# OSO-MISC-21-008_Hiking_Log.net
KiCad netlist of a schematic drawn in EAGLE
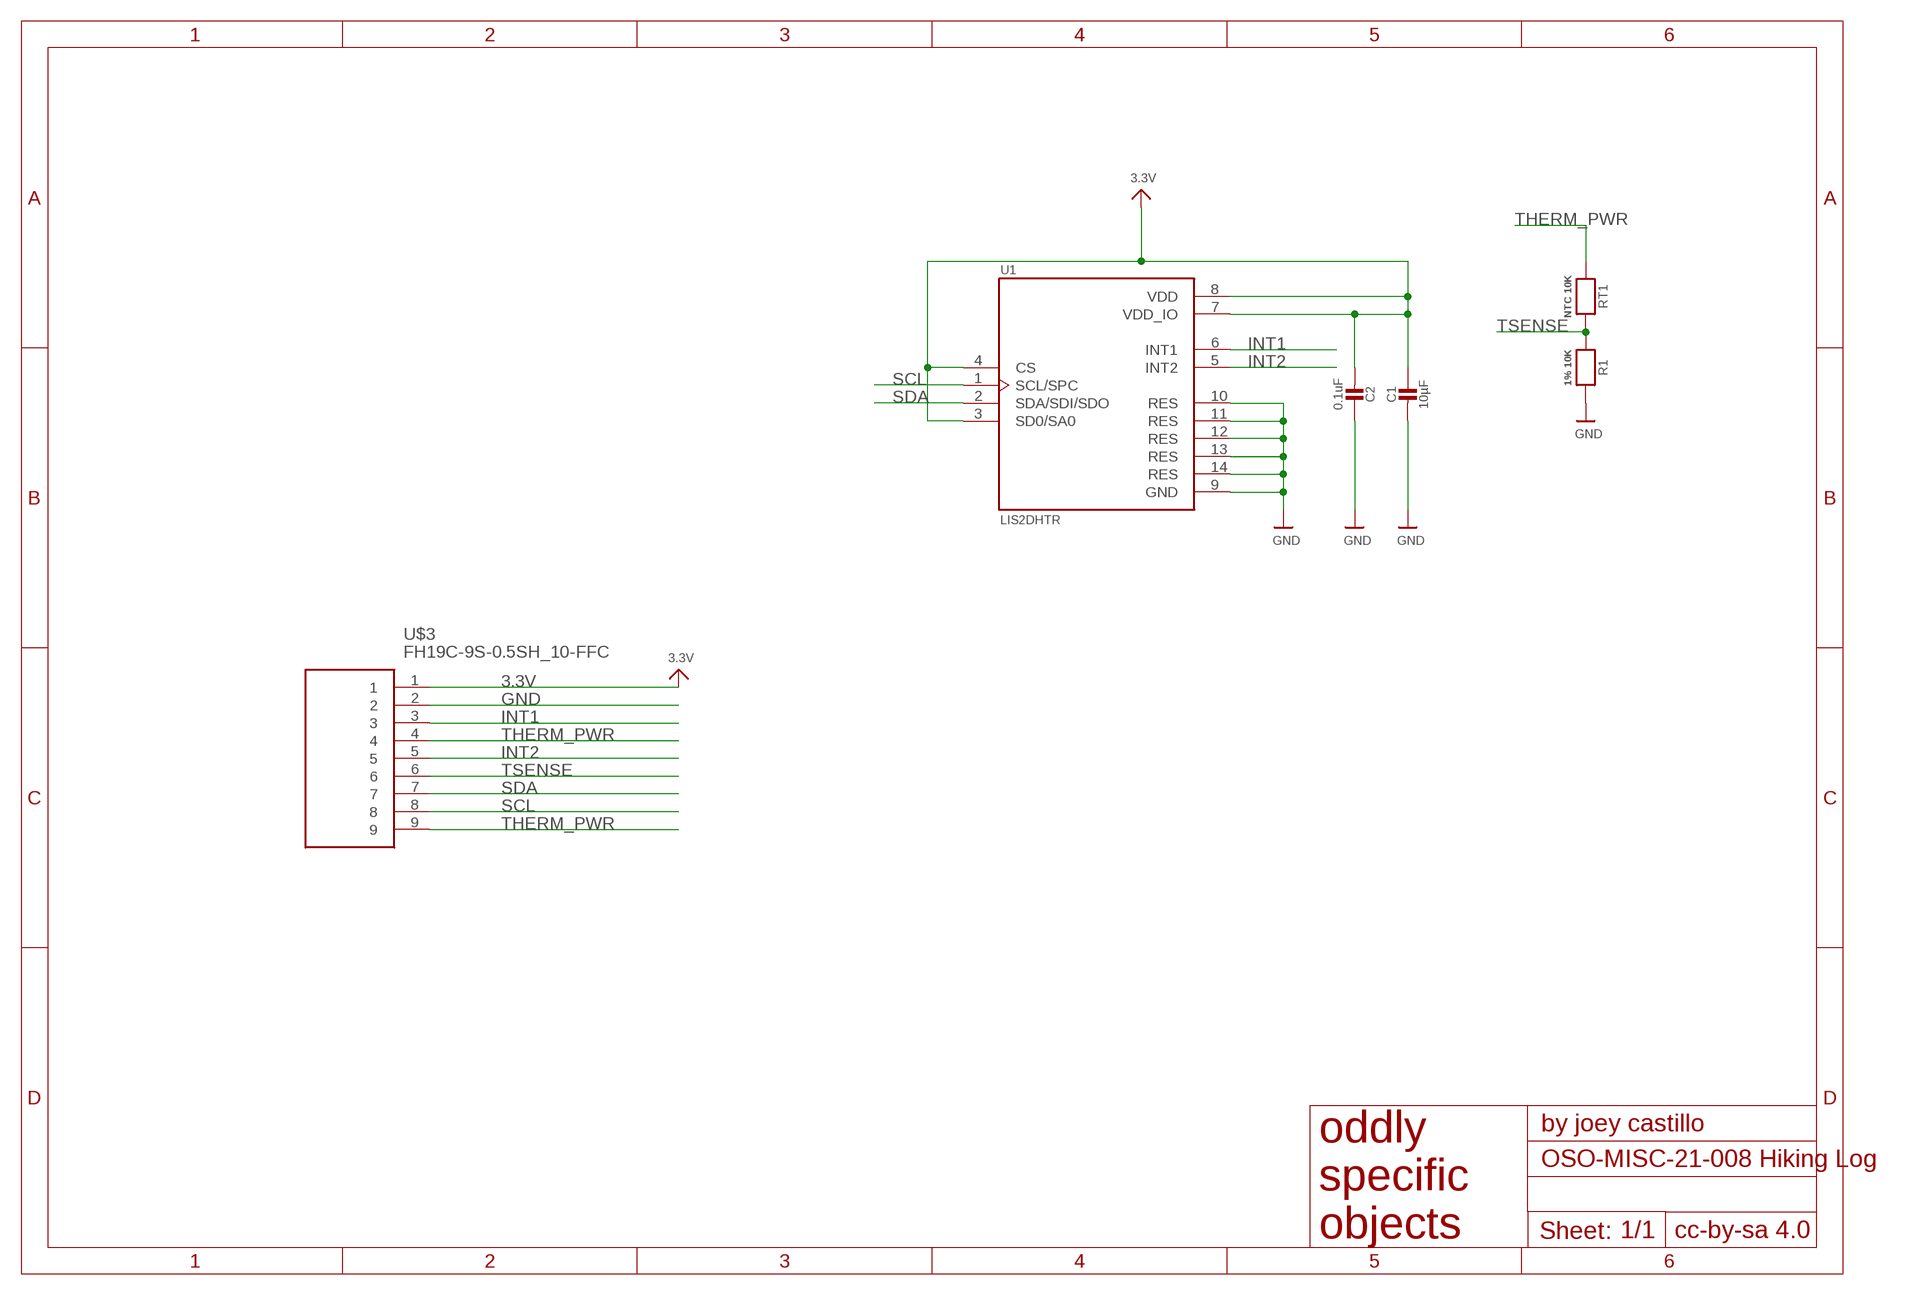
[diagram p0: schematic, sheet 1]

(export (version "E")
  (design (tool "Eeschema 10.0.6"))
  (components
    (comp (ref "C1")
      (value "10µF")
      (footprint "eagle-import:_0402MP")
      (libsource (lib "eagle-import") (part "CAP_CERAMIC_0402MP"))
    )
    (comp (ref "C2")
      (value "0.1uF")
      (footprint "eagle-import:_0402MP")
      (libsource (lib "eagle-import") (part "CAP_CERAMIC_0402MP"))
    )
    (comp (ref "R1")
      (value "1% 10K")
      (footprint "eagle-import:_0402MP")
      (libsource (lib "eagle-import") (part "RESISTOR_0402MP"))
    )
    (comp (ref "RT1")
      (value "NTC 10K")
      (footprint "eagle-import:_0402MP")
      (libsource (lib "eagle-import") (part "RESISTOR_0402MP"))
    )
    (comp (ref "U$3")
      (value "FH19C-9S-0.5SH_10-FFC")
      (footprint "eagle-import:FH19C9S05SH10-FFC")
      (libsource (lib "eagle-import") (part "FH19C-9S-0.5SH_10-FFC"))
    )
    (comp (ref "U1")
      (value "LIS2DHTR")
      (footprint "eagle-import:PQFN35P200X200X100-14N")
      (fields (field (name "DIGI-KEY_PART_NUMBER") "497-13795-1-ND") (field (name "MF") "STMicroelectronics"))
      (libsource (lib "eagle-import") (part "LIS2DHTR"))
    )
  )
  (nets
    (net (code "1") (name "/INT1") (class "Default")
      (node (ref "U$3") (pin "3") (pinfunction "3_3") (pintype "bidirectional"))
      (node (ref "U1") (pin "6") (pinfunction "INT1_6") (pintype "output"))
    )
    (net (code "2") (name "/INT2") (class "Default")
      (node (ref "U$3") (pin "5") (pinfunction "5_5") (pintype "bidirectional"))
      (node (ref "U1") (pin "5") (pinfunction "INT2_5") (pintype "output"))
    )
    (net (code "3") (name "/SCL") (class "Default")
      (node (ref "U$3") (pin "8") (pinfunction "8_8") (pintype "bidirectional"))
      (node (ref "U1") (pin "1") (pinfunction "SCL/SPC_1") (pintype "input"))
    )
    (net (code "4") (name "/SDA") (class "Default")
      (node (ref "U$3") (pin "7") (pinfunction "7_7") (pintype "bidirectional"))
      (node (ref "U1") (pin "2") (pinfunction "SDA/SDI/SDO_2") (pintype "bidirectional"))
    )
    (net (code "5") (name "/THERM_PWR") (class "Default")
      (node (ref "RT1") (pin "1") (pinfunction "1_1") (pintype "passive"))
      (node (ref "U$3") (pin "4") (pinfunction "4_4") (pintype "bidirectional"))
      (node (ref "U$3") (pin "9") (pinfunction "9_9") (pintype "bidirectional"))
    )
    (net (code "6") (name "/TSENSE") (class "Default")
      (node (ref "R1") (pin "1") (pinfunction "1_1") (pintype "passive"))
      (node (ref "RT1") (pin "2") (pinfunction "2_2") (pintype "passive"))
      (node (ref "U$3") (pin "6") (pinfunction "6_6") (pintype "bidirectional"))
    )
    (net (code "7") (name "3.3V") (class "Default")
      (node (ref "C1") (pin "1") (pinfunction "1_1") (pintype "passive"))
      (node (ref "C2") (pin "2") (pinfunction "2_2") (pintype "passive"))
      (node (ref "U$3") (pin "1") (pinfunction "1_1") (pintype "bidirectional"))
      (node (ref "U1") (pin "3") (pinfunction "SD0/SA0_3") (pintype "output"))
      (node (ref "U1") (pin "4") (pinfunction "CS_4") (pintype "input"))
      (node (ref "U1") (pin "7") (pinfunction "VDD_IO_7") (pintype "power_in"))
      (node (ref "U1") (pin "8") (pinfunction "VDD_8") (pintype "power_in"))
    )
    (net (code "8") (name "GND") (class "Default")
      (node (ref "C1") (pin "2") (pinfunction "2_2") (pintype "passive"))
      (node (ref "C2") (pin "1") (pinfunction "1_1") (pintype "passive"))
      (node (ref "R1") (pin "2") (pinfunction "2_2") (pintype "passive"))
      (node (ref "U$3") (pin "2") (pinfunction "2_2") (pintype "bidirectional"))
      (node (ref "U1") (pin "10") (pinfunction "RES_10") (pintype "power_in"))
      (node (ref "U1") (pin "11") (pinfunction "RES_11") (pintype "power_in"))
      (node (ref "U1") (pin "12") (pinfunction "RES_12") (pintype "power_in"))
      (node (ref "U1") (pin "13") (pinfunction "RES_13") (pintype "power_in"))
      (node (ref "U1") (pin "14") (pinfunction "RES_14") (pintype "power_in"))
      (node (ref "U1") (pin "9") (pinfunction "GND_9") (pintype "power_in"))
    )
  )
)
